# STM32_microcontroller_IOs.net
KiCad netlist of a schematic drawn in Altium Designer
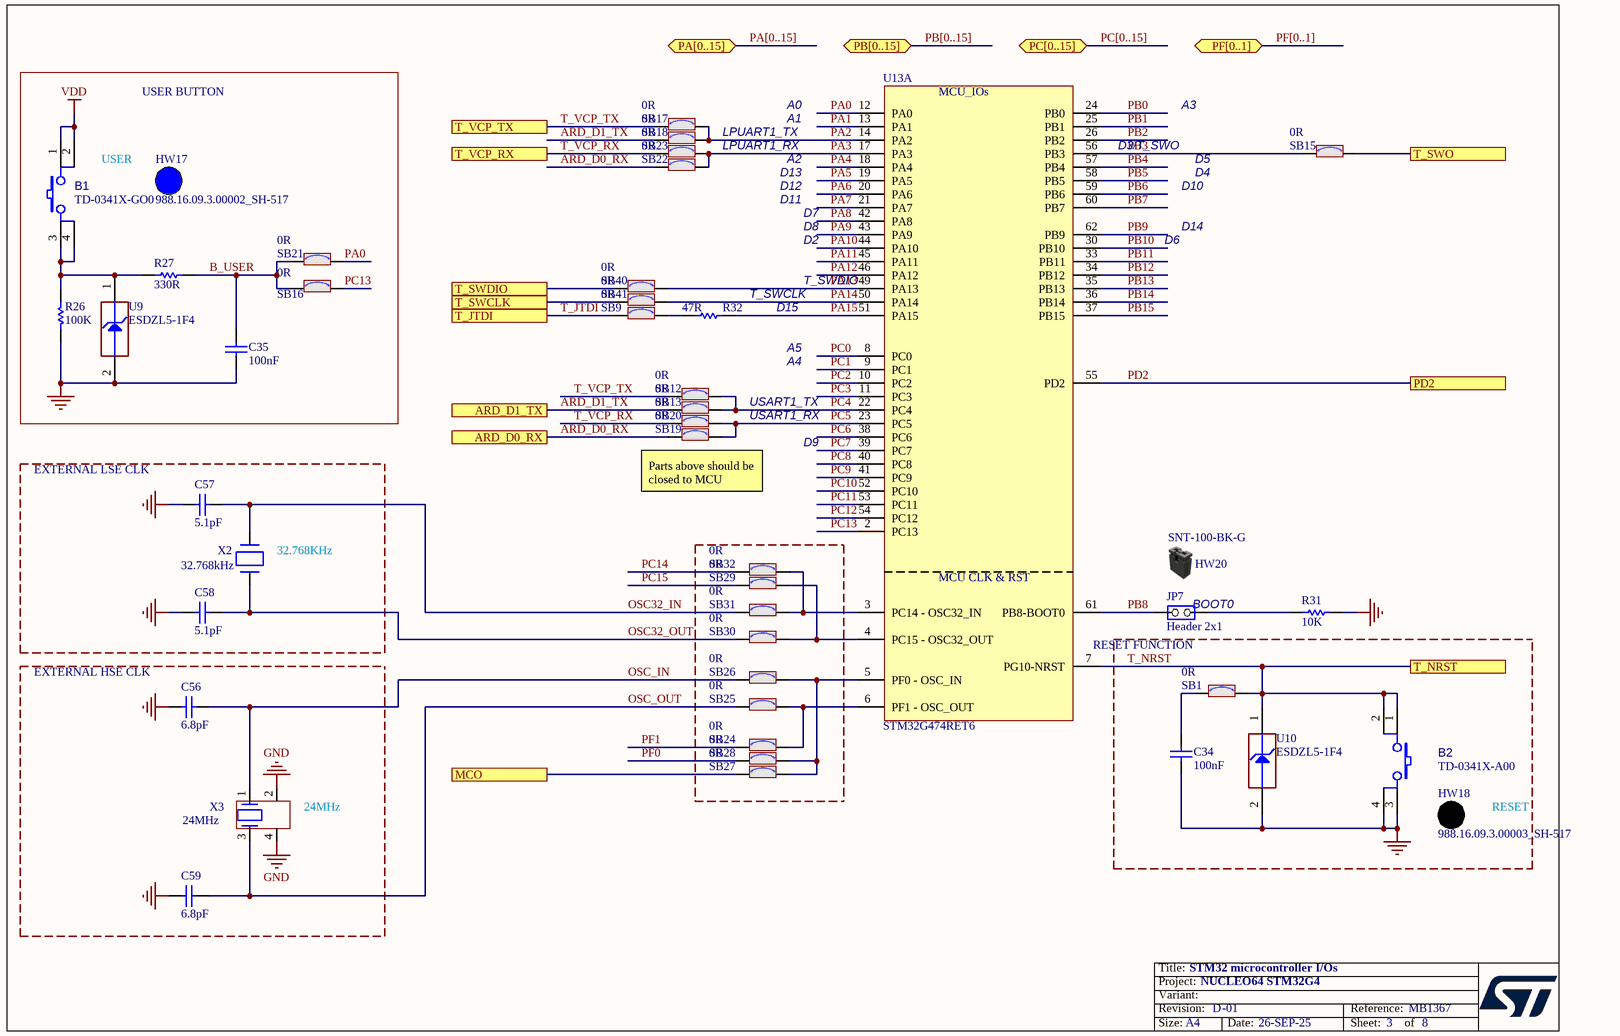
[diagram p0: STM32_microcontroller_IOs.SchDoc]

(export (version "E")
  (design (tool "Eeschema 10.0.6"))
  (components
    (comp (ref "B1")
      (value "TD-0341X-GO0")
      (footprint "SWI_WEALTHMETAL_TD-0341_4P_BLUE")
      (description "Non-Open Push-Button 0.1A 24V")
      (fields
        (field (name "INTERNAL_PART_NUMBER") "MCD-00002")
        (field (name "MANUFACTURER") "WEALTHMETAL")
        (field (name "PROVIDED_BY") "SUBCO")
      )
      (libsource (lib "MCD_PARTS_database") (part "SW-PUSH-CMS"))
    )
    (comp (ref "B2")
      (value "TD-0341X-A00")
      (footprint "SWI_WEALTHMETAL_TD-0341_4P_BLACK")
      (description "Non-Open Push-Button 0.1A 24V BLACK")
      (fields
        (field (name "INTERNAL_PART_NUMBER") "MCD-00001")
        (field (name "MANUFACTURER") "WEALTHMETAL")
        (field (name "PROVIDED_BY") "SUBCO")
      )
      (libsource (lib "MCD_PARTS_database") (part "SW-PUSH-CMS"))
    )
    (comp (ref "C34")
      (value "100nF")
      (footprint "C0402")
      (description "Capacitor, MLCC, 100nF, 16V, X7R, +/-10%, 0402, T=0.5mm")
      (fields
        (field (name "INTERNAL_PART_NUMBER") "MCD-00006")
        (field (name "MANUFACTURER_PART_NUMBER") "CC0402KRX7R7BB104")
      )
      (libsource (lib "MCD_PARTS_database") (part "Capacitor"))
    )
    (comp (ref "C35")
      (value "100nF")
      (footprint "C0402")
      (description "Capacitor, MLCC, 100nF, 16V, X7R, +/-10%, 0402, T=0.5mm")
      (fields
        (field (name "INTERNAL_PART_NUMBER") "MCD-00006")
        (field (name "MANUFACTURER_PART_NUMBER") "CC0402KRX7R7BB104")
      )
      (libsource (lib "MCD_PARTS_database") (part "Capacitor"))
    )
    (comp (ref "C56")
      (value "6.8pF")
      (footprint "C0402")
      (description "Capacitor, MLCC, 6.8pF, 50V, NPO, +-0.25pF, 0402, T=0.5mm")
      (fields
        (field (name "INTERNAL_PART_NUMBER") "MCD-00674")
        (field (name "MANUFACTURER_PART_NUMBER") "CC0402CRNPO9BN6R8")
        (field (name "PROVIDED_BY") "SUBCO")
      )
      (libsource (lib "MCD_PARTS_database") (part "Capacitor"))
    )
    (comp (ref "C57")
      (value "5.1pF")
      (footprint "C0402")
      (description "Capacitor, MLCC, 5.1pF, 50V, NPO, +-0.25pF, 0402, T=0.5mm")
      (fields
        (field (name "INTERNAL_PART_NUMBER") "MCD-00003")
        (field (name "MANUFACTURER_PART_NUMBER") "CC0402CRNPO9BN5R1")
        (field (name "PROVIDED_BY") "SUBCO")
      )
      (libsource (lib "MCD_PARTS_database") (part "Capacitor"))
    )
    (comp (ref "C58")
      (value "5.1pF")
      (footprint "C0402")
      (description "Capacitor, MLCC, 5.1pF, 50V, NPO, +-0.25pF, 0402, T=0.5mm")
      (fields
        (field (name "INTERNAL_PART_NUMBER") "MCD-00003")
        (field (name "MANUFACTURER_PART_NUMBER") "CC0402CRNPO9BN5R1")
        (field (name "PROVIDED_BY") "SUBCO")
      )
      (libsource (lib "MCD_PARTS_database") (part "Capacitor"))
    )
    (comp (ref "C59")
      (value "6.8pF")
      (footprint "C0402")
      (description "Capacitor, MLCC, 6.8pF, 50V, NPO, +-0.25pF, 0402, T=0.5mm")
      (fields
        (field (name "INTERNAL_PART_NUMBER") "MCD-00674")
        (field (name "MANUFACTURER_PART_NUMBER") "CC0402CRNPO9BN6R8")
        (field (name "PROVIDED_BY") "SUBCO")
      )
      (libsource (lib "MCD_PARTS_database") (part "Capacitor"))
    )
    (comp (ref "HW17")
      (value "988.16.09.3.00002_SH-517")
      (description "Blue Hat for switch TD0341X-G01-BLU")
      (fields
        (field (name "INTERNAL_PART_NUMBER") "MCD-00634")
        (field (name "MANUFACTURER") "_A_JIUBABA")
        (field (name "PROVIDED_BY") "SUBCO")
      )
      (libsource (lib "MCD_PARTS_database") (part "BUTTON_HAT_BLUE"))
    )
    (comp (ref "HW18")
      (value "988.16.09.3.00003_SH-517")
      (description "Black Hat for switch TD0341X-G01-BLA")
      (fields
        (field (name "INTERNAL_PART_NUMBER") "MCD-00635")
        (field (name "MANUFACTURER") "_A_JIUBABA")
        (field (name "PROVIDED_BY") "SUBCO")
      )
      (libsource (lib "MCD_PARTS_database") (part "BUTTON_HAT_BLACK"))
    )
    (comp (ref "HW20")
      (value "SNT-100-BK-G")
      (description "SHUNT 2.54mm BLACK")
      (fields
        (field (name "INTERNAL_PART_NUMBER") "MCD-00043")
        (field (name "MANUFACTURER") "SAMTEC")
        (field (name "PROVIDED_BY") "Subcon")
      )
      (libsource (lib "MCD_PARTS_database") (part "Shunt Black 2.54mm"))
    )
    (comp (ref "JP7")
      (value "Header 2x1")
      (footprint "CON_SAMTEC_TSW-102-07-G-S")
      (description "Header, 2x1, 2,54mm, VR, TH, Height 5.84mm/2.54mm")
      (fields
        (field (name "INTERNAL_PART_NUMBER") "MCD-00045")
        (field (name "MANUFACTURER_PART_NUMBER") "TSW-102-07-G-S")
        (field (name "PROVIDED_BY") "Subcon")
      )
      (libsource (lib "MCD_PARTS_database") (part "Jumper_Header 2x1"))
    )
    (comp (ref "R26")
      (value "100K")
      (footprint "R0603")
      (description "Resistor,100K,0603,1%,1/10W")
      (fields
        (field (name "INTERNAL_PART_NUMBER") "MCD-00223")
        (field (name "MANUFACTURER_PART_NUMBER") "RC0603FR-07100KL")
        (field (name "PROVIDED_BY") "Subcon")
      )
      (libsource (lib "MCD_PARTS_database") (part "Resistor"))
    )
    (comp (ref "R27")
      (value "330R")
      (footprint "R0603")
      (description "Resistor,330R,0603,1%,1/10W")
      (fields
        (field (name "INTERNAL_PART_NUMBER") "MCD-00197")
        (field (name "MANUFACTURER_PART_NUMBER") "RC0603FR-07330RL")
        (field (name "PROVIDED_BY") "Subcon")
      )
      (libsource (lib "MCD_PARTS_database") (part "Resistor"))
    )
    (comp (ref "R31")
      (value "10K")
      (footprint "R0603")
      (description "Resistor,10K,0603,1%,1/10W")
      (fields
        (field (name "INTERNAL_PART_NUMBER") "MCD-00220")
        (field (name "MANUFACTURER_PART_NUMBER") "RC0603FR-0710KL")
        (field (name "PROVIDED_BY") "Subcon")
      )
      (libsource (lib "MCD_PARTS_database") (part "Resistor"))
    )
    (comp (ref "R32")
      (value "47R")
      (footprint "R0402")
      (description "Resistor,47R,0402,1%,1/16W")
      (fields
        (field (name "INTERNAL_PART_NUMBER") "MCD-00481")
        (field (name "MANUFACTURER_PART_NUMBER") "RC0402FR-0747RL")
        (field (name "PROVIDED_BY") "SUBCO")
      )
      (libsource (lib "MCD_PARTS_database") (part "Resistor"))
    )
    (comp (ref "SB1")
      (value "0R")
      (footprint "SOLDER-BRIDGE_R0603-0R")
      (description "Solder Bridge ON")
      (fields
        (field (name "INTERNAL_PART_NUMBER") "MCD-00071")
        (field (name "MANUFACTURER_PART_NUMBER") "RC0603JR-070RL")
        (field (name "PROVIDED_BY") "SUBCO")
      )
      (libsource (lib "MCD_PARTS_database") (part "SB_ON"))
    )
    (comp (ref "SB9")
      (value "0R")
      (footprint "SOLDER-BRIDGE_R0603-0R")
      (description "Solder Bridge ON")
      (fields
        (field (name "INTERNAL_PART_NUMBER") "MCD-00071")
        (field (name "MANUFACTURER_PART_NUMBER") "RC0603JR-070RL")
        (field (name "PROVIDED_BY") "SUBCO")
      )
      (libsource (lib "MCD_PARTS_database") (part "SB_ON"))
    )
    (comp (ref "SB12")
      (value "0R")
      (footprint "SOLDER-BRIDGE_R0603-0R")
      (description "Solder Bridge ON")
      (fields
        (field (name "INTERNAL_PART_NUMBER") "MCD-00071")
        (field (name "MANUFACTURER_PART_NUMBER") "RC0603JR-070RL")
        (field (name "PROVIDED_BY") "SUBCO")
      )
      (libsource (lib "MCD_PARTS_database") (part "SB_ON"))
    )
    (comp (ref "SB13")
      (value "0R")
      (footprint "SOLDER-BRIDGE_R0603-0R")
      (description "Solder Bridge ON")
      (fields
        (field (name "INTERNAL_PART_NUMBER") "MCD-00071")
        (field (name "MANUFACTURER_PART_NUMBER") "RC0603JR-070RL")
        (field (name "PROVIDED_BY") "SUBCO")
      )
      (libsource (lib "") (part "SB_ON_1"))
    )
    (comp (ref "SB15")
      (value "0R")
      (footprint "SOLDER-BRIDGE_R0603-0R")
      (description "Solder Bridge ON")
      (fields
        (field (name "INTERNAL_PART_NUMBER") "MCD-00071")
        (field (name "MANUFACTURER_PART_NUMBER") "RC0603JR-070RL")
        (field (name "PROVIDED_BY") "SUBCO")
      )
      (libsource (lib "MCD_PARTS_database") (part "SB_ON"))
    )
    (comp (ref "SB16")
      (value "0R")
      (footprint "SOLDER-BRIDGE_R0603-0R")
      (description "Solder Bridge ON")
      (fields
        (field (name "INTERNAL_PART_NUMBER") "MCD-00071")
        (field (name "MANUFACTURER_PART_NUMBER") "RC0603JR-070RL")
        (field (name "PROVIDED_BY") "SUBCO")
      )
      (libsource (lib "MCD_PARTS_database") (part "SB_ON"))
    )
    (comp (ref "SB17")
      (value "0R")
      (footprint "SOLDER-BRIDGE_R0603-0R")
      (description "Solder Bridge ON")
      (fields
        (field (name "INTERNAL_PART_NUMBER") "MCD-00071")
        (field (name "MANUFACTURER_PART_NUMBER") "RC0603JR-070RL")
        (field (name "PROVIDED_BY") "SUBCO")
      )
      (libsource (lib "MCD_PARTS_database") (part "SB_ON"))
    )
    (comp (ref "SB18")
      (value "0R")
      (footprint "SOLDER-BRIDGE_R0603-0R")
      (description "Solder Bridge ON")
      (fields
        (field (name "INTERNAL_PART_NUMBER") "MCD-00071")
        (field (name "MANUFACTURER_PART_NUMBER") "RC0603JR-070RL")
        (field (name "PROVIDED_BY") "SUBCO")
      )
      (libsource (lib "") (part "SB_ON_1"))
    )
    (comp (ref "SB19")
      (value "0R")
      (footprint "SOLDER-BRIDGE_R0603-0R")
      (description "Solder Bridge ON")
      (fields
        (field (name "INTERNAL_PART_NUMBER") "MCD-00071")
        (field (name "MANUFACTURER_PART_NUMBER") "RC0603JR-070RL")
        (field (name "PROVIDED_BY") "SUBCO")
      )
      (libsource (lib "") (part "SB_ON_1"))
    )
    (comp (ref "SB20")
      (value "0R")
      (footprint "SOLDER-BRIDGE_R0603-0R")
      (description "Solder Bridge ON")
      (fields
        (field (name "INTERNAL_PART_NUMBER") "MCD-00071")
        (field (name "MANUFACTURER_PART_NUMBER") "RC0603JR-070RL")
        (field (name "PROVIDED_BY") "SUBCO")
      )
      (libsource (lib "MCD_PARTS_database") (part "SB_ON"))
    )
    (comp (ref "SB21")
      (value "0R")
      (footprint "SOLDER-BRIDGE_R0603-0R")
      (description "Solder Bridge ON")
      (fields
        (field (name "INTERNAL_PART_NUMBER") "MCD-00071")
        (field (name "MANUFACTURER_PART_NUMBER") "RC0603JR-070RL")
        (field (name "PROVIDED_BY") "SUBCO")
      )
      (libsource (lib "MCD_PARTS_database") (part "SB_ON"))
    )
    (comp (ref "SB22")
      (value "0R")
      (footprint "SOLDER-BRIDGE_R0603-0R")
      (description "Solder Bridge ON")
      (fields
        (field (name "INTERNAL_PART_NUMBER") "MCD-00071")
        (field (name "MANUFACTURER_PART_NUMBER") "RC0603JR-070RL")
        (field (name "PROVIDED_BY") "SUBCO")
      )
      (libsource (lib "") (part "SB_ON_1"))
    )
    (comp (ref "SB23")
      (value "0R")
      (footprint "SOLDER-BRIDGE_R0603-0R")
      (description "Solder Bridge ON")
      (fields
        (field (name "INTERNAL_PART_NUMBER") "MCD-00071")
        (field (name "MANUFACTURER_PART_NUMBER") "RC0603JR-070RL")
        (field (name "PROVIDED_BY") "SUBCO")
      )
      (libsource (lib "MCD_PARTS_database") (part "SB_ON"))
    )
    (comp (ref "SB24")
      (value "0R")
      (footprint "SOLDER-BRIDGE_R0603-0R")
      (description "Solder Bridge ON")
      (fields
        (field (name "INTERNAL_PART_NUMBER") "MCD-00071")
        (field (name "MANUFACTURER_PART_NUMBER") "RC0603JR-070RL")
        (field (name "PROVIDED_BY") "SUBCO")
      )
      (libsource (lib "MCD_PARTS_database") (part "SB_ON"))
    )
    (comp (ref "SB25")
      (value "0R")
      (footprint "SOLDER-BRIDGE_R0603-0R")
      (description "Solder Bridge ON")
      (fields
        (field (name "INTERNAL_PART_NUMBER") "MCD-00071")
        (field (name "MANUFACTURER_PART_NUMBER") "RC0603JR-070RL")
        (field (name "PROVIDED_BY") "SUBCO")
      )
      (libsource (lib "MCD_PARTS_database") (part "SB_ON"))
    )
    (comp (ref "SB26")
      (value "0R")
      (footprint "SOLDER-BRIDGE_R0603-0R")
      (description "Solder Bridge ON")
      (fields
        (field (name "INTERNAL_PART_NUMBER") "MCD-00071")
        (field (name "MANUFACTURER_PART_NUMBER") "RC0603JR-070RL")
        (field (name "PROVIDED_BY") "SUBCO")
      )
      (libsource (lib "MCD_PARTS_database") (part "SB_ON"))
    )
    (comp (ref "SB27")
      (value "0R")
      (footprint "SOLDER-BRIDGE_R0603-0R")
      (description "Solder Bridge ON")
      (fields
        (field (name "INTERNAL_PART_NUMBER") "MCD-00071")
        (field (name "MANUFACTURER_PART_NUMBER") "RC0603JR-070RL")
        (field (name "PROVIDED_BY") "SUBCO")
      )
      (libsource (lib "MCD_PARTS_database") (part "SB_ON"))
    )
    (comp (ref "SB28")
      (value "0R")
      (footprint "SOLDER-BRIDGE_R0603-0R")
      (description "Solder Bridge ON")
      (fields
        (field (name "INTERNAL_PART_NUMBER") "MCD-00071")
        (field (name "MANUFACTURER_PART_NUMBER") "RC0603JR-070RL")
        (field (name "PROVIDED_BY") "SUBCO")
      )
      (libsource (lib "MCD_PARTS_database") (part "SB_ON"))
    )
    (comp (ref "SB29")
      (value "0R")
      (footprint "SOLDER-BRIDGE_R0603-0R")
      (description "Solder Bridge ON")
      (fields
        (field (name "INTERNAL_PART_NUMBER") "MCD-00071")
        (field (name "MANUFACTURER_PART_NUMBER") "RC0603JR-070RL")
        (field (name "PROVIDED_BY") "SUBCO")
      )
      (libsource (lib "MCD_PARTS_database") (part "SB_ON"))
    )
    (comp (ref "SB30")
      (value "0R")
      (footprint "SOLDER-BRIDGE_R0603-0R")
      (description "Solder Bridge ON")
      (fields
        (field (name "INTERNAL_PART_NUMBER") "MCD-00071")
        (field (name "MANUFACTURER_PART_NUMBER") "RC0603JR-070RL")
        (field (name "PROVIDED_BY") "SUBCO")
      )
      (libsource (lib "MCD_PARTS_database") (part "SB_ON"))
    )
    (comp (ref "SB31")
      (value "0R")
      (footprint "SOLDER-BRIDGE_R0603-0R")
      (description "Solder Bridge ON")
      (fields
        (field (name "INTERNAL_PART_NUMBER") "MCD-00071")
        (field (name "MANUFACTURER_PART_NUMBER") "RC0603JR-070RL")
        (field (name "PROVIDED_BY") "SUBCO")
      )
      (libsource (lib "MCD_PARTS_database") (part "SB_ON"))
    )
    (comp (ref "SB32")
      (value "0R")
      (footprint "SOLDER-BRIDGE_R0603-0R")
      (description "Solder Bridge ON")
      (fields
        (field (name "INTERNAL_PART_NUMBER") "MCD-00071")
        (field (name "MANUFACTURER_PART_NUMBER") "RC0603JR-070RL")
        (field (name "PROVIDED_BY") "SUBCO")
      )
      (libsource (lib "MCD_PARTS_database") (part "SB_ON"))
    )
    (comp (ref "SB40")
      (value "0R")
      (footprint "SOLDER-BRIDGE_R0603-0R")
      (description "Solder Bridge ON")
      (fields
        (field (name "INTERNAL_PART_NUMBER") "MCD-00071")
        (field (name "MANUFACTURER_PART_NUMBER") "RC0603JR-070RL")
        (field (name "PROVIDED_BY") "SUBCO")
      )
      (libsource (lib "MCD_PARTS_database") (part "SB_ON"))
    )
    (comp (ref "SB41")
      (value "0R")
      (footprint "SOLDER-BRIDGE_R0603-0R")
      (description "Solder Bridge ON")
      (fields
        (field (name "INTERNAL_PART_NUMBER") "MCD-00071")
        (field (name "MANUFACTURER_PART_NUMBER") "RC0603JR-070RL")
        (field (name "PROVIDED_BY") "SUBCO")
      )
      (libsource (lib "MCD_PARTS_database") (part "SB_ON"))
    )
    (comp (ref "U9")
      (value "ESDZL5-1F4")
      (footprint "ESD_0201_H0P3_1K_2A")
      (description "Diode, ESD TVS, 5V5, 100nA, 10V, 0201")
      (fields
        (field (name "INTERNAL_PART_NUMBER") "MCD-03501")
        (field (name "MANUFACTURER") "STMICROELECTRONICS")
      )
      (libsource (lib "MCD_PARTS_database") (part "ESD-TRANSIL"))
    )
    (comp (ref "U10")
      (value "ESDZL5-1F4")
      (footprint "ESD_0201_H0P3_1K_2A")
      (description "Diode, ESD TVS, 5V5, 100nA, 10V, 0201")
      (fields
        (field (name "INTERNAL_PART_NUMBER") "MCD-03501")
        (field (name "MANUFACTURER") "STMICROELECTRONICS")
      )
      (libsource (lib "MCD_PARTS_database") (part "ESD-TRANSIL"))
    )
    (comp (ref "U13")
      (value "STM32G474RET6")
      (footprint "ICC_LQFP64_10X10_P050_SOCKET_YAMAICHI_IC149-064-069-B5_NM")
      (description "STM32G474, LQFP64 package,  3D IC footprint with 2D socket footprint.")
      (fields
        (field (name "INTERNAL_PART_NUMBER") "MCD-01243")
        (field (name "MANUFACTURER") "STMICROELECTRONICS")
        (field (name "PROVIDED_BY") "SUBCO with ST control")
      )
      (libsource (lib "MCD_PARTS_database") (part "STM32G4xx_LQFP64"))
    )
    (comp (ref "X2")
      (value "32.768kHz")
      (footprint "CRY_NX3215SA_2P")
      (description "Crystal 32.768kHz, 6pF, +-20ppm, 50Kohms max, SMD")
      (fields
        (field (name "INTERNAL_PART_NUMBER") "MCD-00091")
        (field (name "MANUFACTURER_PART_NUMBER") "NX3215SA-32.768KHz-EXS00A-MU00525")
        (field (name "PROVIDED_BY") "SUBCO")
      )
      (libsource (lib "MCD_PARTS_database") (part "XTAL_2_PINS"))
    )
    (comp (ref "X3")
      (value "24MHz")
      (footprint "CRY_NX2016SA_4P")
      (description "Crystal 24MHz, 6pF, +-20ppm, 80ohms max, SMD")
      (fields
        (field (name "INTERNAL_PART_NUMBER") "MCD-01036")
        (field (name "MANUFACTURER_PART_NUMBER") "NX2016SA-24MHz-EXS00A-CS10820")
        (field (name "PROVIDED_BY") "SUBCO")
      )
      (libsource (lib "MCD_PARTS_database") (part "XTAL_4_PINS"))
    )
  )
  (nets
    (net (code "1") (name "/ARD_D0_RX") (class "Default")
      (node (ref "SB19") (pin "2") (pinfunction "2_2") (pintype "passive"))
      (node (ref "SB22") (pin "2") (pinfunction "2_2") (pintype "passive"))
    )
    (net (code "2") (name "/ARD_D1_TX") (class "Default")
      (node (ref "SB13") (pin "2") (pinfunction "2_2") (pintype "passive"))
      (node (ref "SB18") (pin "2") (pinfunction "2_2") (pintype "passive"))
    )
    (net (code "3") (name "/B_USER") (class "Default")
      (node (ref "C35") (pin "2") (pinfunction "2_2") (pintype "passive"))
      (node (ref "R27") (pin "2") (pinfunction "2_2") (pintype "passive"))
      (node (ref "SB16") (pin "1") (pinfunction "1_1") (pintype "passive"))
      (node (ref "SB21") (pin "1") (pinfunction "1_1") (pintype "passive"))
    )
    (net (code "4") (name "/MCO") (class "Default")
      (node (ref "SB27") (pin "1") (pinfunction "1_1") (pintype "passive"))
    )
    (net (code "5") (name "/OSC32_IN") (class "Default")
      (node (ref "C57") (pin "1") (pinfunction "1_1") (pintype "passive"))
      (node (ref "SB31") (pin "1") (pinfunction "1_1") (pintype "passive"))
      (node (ref "X2") (pin "1") (pinfunction "X1_1") (pintype "passive"))
    )
    (net (code "6") (name "/OSC32_OUT") (class "Default")
      (node (ref "C58") (pin "1") (pinfunction "1_1") (pintype "passive"))
      (node (ref "SB30") (pin "1") (pinfunction "1_1") (pintype "passive"))
      (node (ref "X2") (pin "2") (pinfunction "X2_2") (pintype "passive"))
    )
    (net (code "7") (name "/OSC_IN") (class "Default")
      (node (ref "C56") (pin "2") (pinfunction "2_2") (pintype "passive"))
      (node (ref "SB26") (pin "1") (pinfunction "1_1") (pintype "passive"))
      (node (ref "X3") (pin "1") (pinfunction "1_1") (pintype "passive"))
    )
    (net (code "8") (name "/OSC_OUT") (class "Default")
      (node (ref "C59") (pin "2") (pinfunction "2_2") (pintype "passive"))
      (node (ref "SB25") (pin "1") (pinfunction "1_1") (pintype "passive"))
      (node (ref "X3") (pin "3") (pinfunction "3_3") (pintype "passive"))
    )
    (net (code "9") (name "/PA0") (class "Default")
      (node (ref "SB21") (pin "2") (pinfunction "2_2") (pintype "passive"))
      (node (ref "U13") (pin "12") (pinfunction "PA0_12") (pintype "passive"))
    )
    (net (code "10") (name "/PA1") (class "Default")
      (node (ref "U13") (pin "13") (pinfunction "PA1_13") (pintype "passive"))
    )
    (net (code "11") (name "/PA2") (class "Default")
      (node (ref "SB17") (pin "2") (pinfunction "2_2") (pintype "passive"))
      (node (ref "SB18") (pin "1") (pinfunction "1_1") (pintype "passive"))
      (node (ref "U13") (pin "14") (pinfunction "PA2_14") (pintype "passive"))
    )
    (net (code "12") (name "/PA3") (class "Default")
      (node (ref "SB22") (pin "1") (pinfunction "1_1") (pintype "passive"))
      (node (ref "SB23") (pin "2") (pinfunction "2_2") (pintype "passive"))
      (node (ref "U13") (pin "17") (pinfunction "PA3_17") (pintype "passive"))
    )
    (net (code "13") (name "/PA4") (class "Default")
      (node (ref "U13") (pin "18") (pinfunction "PA4_18") (pintype "passive"))
    )
    (net (code "14") (name "/PA5") (class "Default")
      (node (ref "U13") (pin "19") (pinfunction "PA5_19") (pintype "passive"))
    )
    (net (code "15") (name "/PA6") (class "Default")
      (node (ref "U13") (pin "20") (pinfunction "PA6_20") (pintype "passive"))
    )
    (net (code "16") (name "/PA7") (class "Default")
      (node (ref "U13") (pin "21") (pinfunction "PA7_21") (pintype "passive"))
    )
    (net (code "17") (name "/PA8") (class "Default")
      (node (ref "U13") (pin "42") (pinfunction "PA8_42") (pintype "passive"))
    )
    (net (code "18") (name "/PA9") (class "Default")
      (node (ref "U13") (pin "43") (pinfunction "PA9_43") (pintype "passive"))
    )
    (net (code "19") (name "/PA10") (class "Default")
      (node (ref "U13") (pin "44") (pinfunction "PA10_44") (pintype "passive"))
    )
    (net (code "20") (name "/PA11") (class "Default")
      (node (ref "U13") (pin "45") (pinfunction "PA11_45") (pintype "passive"))
    )
    (net (code "21") (name "/PA12") (class "Default")
      (node (ref "U13") (pin "46") (pinfunction "PA12_46") (pintype "passive"))
    )
    (net (code "22") (name "/PA13") (class "Default")
      (node (ref "SB40") (pin "2") (pinfunction "2_2") (pintype "passive"))
      (node (ref "U13") (pin "49") (pinfunction "PA13_49") (pintype "passive"))
    )
    (net (code "23") (name "/PA14") (class "Default")
      (node (ref "SB41") (pin "2") (pinfunction "2_2") (pintype "passive"))
      (node (ref "U13") (pin "50") (pinfunction "PA14_50") (pintype "passive"))
    )
    (net (code "24") (name "/PA15") (class "Default")
      (node (ref "R32") (pin "2") (pinfunction "2_2") (pintype "passive"))
      (node (ref "U13") (pin "51") (pinfunction "PA15_51") (pintype "passive"))
    )
    (net (code "26") (name "/PB0") (class "Default")
      (node (ref "U13") (pin "24") (pinfunction "PB0_24") (pintype "passive"))
    )
    (net (code "27") (name "/PB1") (class "Default")
      (node (ref "U13") (pin "25") (pinfunction "PB1_25") (pintype "passive"))
    )
    (net (code "28") (name "/PB2") (class "Default")
      (node (ref "U13") (pin "26") (pinfunction "PB2_26") (pintype "passive"))
    )
    (net (code "29") (name "/PB3") (class "Default")
      (node (ref "SB15") (pin "1") (pinfunction "1_1") (pintype "passive"))
      (node (ref "U13") (pin "56") (pinfunction "PB3_56") (pintype "passive"))
    )
    (net (code "30") (name "/PB4") (class "Default")
      (node (ref "U13") (pin "57") (pinfunction "PB4_57") (pintype "passive"))
    )
    (net (code "31") (name "/PB5") (class "Default")
      (node (ref "U13") (pin "58") (pinfunction "PB5_58") (pintype "passive"))
    )
    (net (code "32") (name "/PB6") (class "Default")
      (node (ref "U13") (pin "59") (pinfunction "PB6_59") (pintype "passive"))
    )
    (net (code "33") (name "/PB7") (class "Default")
      (node (ref "U13") (pin "60") (pinfunction "PB7_60") (pintype "passive"))
    )
    (net (code "34") (name "/PB8") (class "Default")
      (node (ref "JP7") (pin "1") (pinfunction "COMMON_1") (pintype "passive"))
      (node (ref "U13") (pin "61") (pinfunction "PB8-BOOT0_61") (pintype "passive"))
    )
    (net (code "35") (name "/PB9") (class "Default")
      (node (ref "U13") (pin "62") (pinfunction "PB9_62") (pintype "passive"))
    )
    (net (code "36") (name "/PB10") (class "Default")
      (node (ref "U13") (pin "30") (pinfunction "PB10_30") (pintype "passive"))
    )
    (net (code "37") (name "/PB11") (class "Default")
      (node (ref "U13") (pin "33") (pinfunction "PB11_33") (pintype "passive"))
    )
    (net (code "38") (name "/PB12") (class "Default")
      (node (ref "U13") (pin "34") (pinfunction "PB12_34") (pintype "passive"))
    )
    (net (code "39") (name "/PB13") (class "Default")
      (node (ref "U13") (pin "35") (pinfunction "PB13_35") (pintype "passive"))
    )
    (net (code "40") (name "/PB14") (class "Default")
      (node (ref "U13") (pin "36") (pinfunction "PB14_36") (pintype "passive"))
    )
    (net (code "41") (name "/PB15") (class "Default")
      (node (ref "U13") (pin "37") (pinfunction "PB15_37") (pintype "passive"))
    )
    (net (code "43") (name "/PC0") (class "Default")
      (node (ref "U13") (pin "8") (pinfunction "PC0_8") (pintype "passive"))
    )
    (net (code "44") (name "/PC1") (class "Default")
      (node (ref "U13") (pin "9") (pinfunction "PC1_9") (pintype "passive"))
    )
    (net (code "45") (name "/PC2") (class "Default")
      (node (ref "U13") (pin "10") (pinfunction "PC2_10") (pintype "passive"))
    )
    (net (code "46") (name "/PC3") (class "Default")
      (node (ref "U13") (pin "11") (pinfunction "PC3_11") (pintype "passive"))
    )
    (net (code "47") (name "/PC4") (class "Default")
      (node (ref "SB12") (pin "2") (pinfunction "2_2") (pintype "passive"))
      (node (ref "SB13") (pin "1") (pinfunction "1_1") (pintype "passive"))
      (node (ref "U13") (pin "22") (pinfunction "PC4_22") (pintype "passive"))
    )
    (net (code "48") (name "/PC5") (class "Default")
      (node (ref "SB19") (pin "1") (pinfunction "1_1") (pintype "passive"))
      (node (ref "SB20") (pin "2") (pinfunction "2_2") (pintype "passive"))
      (node (ref "U13") (pin "23") (pinfunction "PC5_23") (pintype "passive"))
    )
    (net (code "49") (name "/PC6") (class "Default")
      (node (ref "U13") (pin "38") (pinfunction "PC6_38") (pintype "passive"))
    )
    (net (code "50") (name "/PC7") (class "Default")
      (node (ref "U13") (pin "39") (pinfunction "PC7_39") (pintype "passive"))
    )
    (net (code "51") (name "/PC8") (class "Default")
      (node (ref "U13") (pin "40") (pinfunction "PC8_40") (pintype "passive"))
    )
    (net (code "52") (name "/PC9") (class "Default")
      (node (ref "U13") (pin "41") (pinfunction "PC9_41") (pintype "passive"))
    )
    (net (code "53") (name "/PC10") (class "Default")
      (node (ref "U13") (pin "52") (pinfunction "PC10_52") (pintype "passive"))
    )
    (net (code "54") (name "/PC11") (class "Default")
      (node (ref "U13") (pin "53") (pinfunction "PC11_53") (pintype "passive"))
    )
    (net (code "55") (name "/PC12") (class "Default")
      (node (ref "U13") (pin "54") (pinfunction "PC12_54") (pintype "passive"))
    )
    (net (code "56") (name "/PC13") (class "Default")
      (node (ref "SB16") (pin "2") (pinfunction "2_2") (pintype "passive"))
      (node (ref "U13") (pin "2") (pinfunction "PC13_2") (pintype "passive"))
    )
    (net (code "57") (name "/PC14") (class "Default")
      (node (ref "SB32") (pin "1") (pinfunction "1_1") (pintype "passive"))
    )
    (net (code "58") (name "/PC15") (class "Default")
      (node (ref "SB29") (pin "1") (pinfunction "1_1") (pintype "passive"))
    )
    (net (code "60") (name "/PD2") (class "Default")
      (node (ref "U13") (pin "55") (pinfunction "PD2_55") (pintype "passive"))
    )
    (net (code "61") (name "/PF0") (class "Default")
      (node (ref "SB28") (pin "1") (pinfunction "1_1") (pintype "passive"))
    )
    (net (code "62") (name "/PF1") (class "Default")
      (node (ref "SB24") (pin "1") (pinfunction "1_1") (pintype "passive"))
    )
    (net (code "64") (name "/T_JTDI") (class "Default")
      (node (ref "SB9") (pin "1") (pinfunction "1_1") (pintype "passive"))
    )
    (net (code "65") (name "/T_NRST") (class "Default")
      (node (ref "B2") (pin "1") (pinfunction "1_1") (pintype "passive"))
      (node (ref "B2") (pin "2") (pinfunction "2_2") (pintype "passive"))
      (node (ref "SB1") (pin "2") (pinfunction "2_2") (pintype "passive"))
      (node (ref "U10") (pin "1") (pinfunction "IO1_1") (pintype "passive"))
      (node (ref "U13") (pin "7") (pinfunction "PG10-NRST_7") (pintype "passive"))
    )
    (net (code "66") (name "/T_SWCLK") (class "Default")
      (node (ref "SB41") (pin "1") (pinfunction "1_1") (pintype "passive"))
    )
    (net (code "67") (name "/T_SWDIO") (class "Default")
      (node (ref "SB40") (pin "1") (pinfunction "1_1") (pintype "passive"))
    )
    (net (code "68") (name "/T_SWO") (class "Default")
      (node (ref "SB15") (pin "2") (pinfunction "2_2") (pintype "passive"))
    )
    (net (code "69") (name "/T_VCP_RX") (class "Default")
      (node (ref "SB20") (pin "1") (pinfunction "1_1") (pintype "passive"))
      (node (ref "SB23") (pin "1") (pinfunction "1_1") (pintype "passive"))
    )
    (net (code "70") (name "/T_VCP_TX") (class "Default")
      (node (ref "SB12") (pin "1") (pinfunction "1_1") (pintype "passive"))
      (node (ref "SB17") (pin "1") (pinfunction "1_1") (pintype "passive"))
    )
    (net (code "71") (name "GND") (class "Default")
      (node (ref "B2") (pin "3") (pinfunction "3_3") (pintype "passive"))
      (node (ref "B2") (pin "4") (pinfunction "4_4") (pintype "passive"))
      (node (ref "C34") (pin "1") (pinfunction "1_1") (pintype "passive"))
      (node (ref "C35") (pin "1") (pinfunction "1_1") (pintype "passive"))
      (node (ref "C56") (pin "1") (pinfunction "1_1") (pintype "passive"))
      (node (ref "C57") (pin "2") (pinfunction "2_2") (pintype "passive"))
      (node (ref "C58") (pin "2") (pinfunction "2_2") (pintype "passive"))
      (node (ref "C59") (pin "1") (pinfunction "1_1") (pintype "passive"))
      (node (ref "R26") (pin "1") (pinfunction "1_1") (pintype "passive"))
      (node (ref "R31") (pin "1") (pinfunction "1_1") (pintype "passive"))
      (node (ref "U10") (pin "2") (pinfunction "GND_2") (pintype "passive"))
      (node (ref "U9") (pin "2") (pinfunction "GND_2") (pintype "passive"))
      (node (ref "X3") (pin "2") (pinfunction "2_2") (pintype "passive"))
      (node (ref "X3") (pin "4") (pinfunction "4_4") (pintype "passive"))
    )
    (net (code "72") (name "Net-(C34-Pad2)") (class "Default")
      (node (ref "C34") (pin "2") (pinfunction "2_2") (pintype "passive"))
      (node (ref "SB1") (pin "1") (pinfunction "1_1") (pintype "passive"))
    )
    (net (code "73") (name "Net-(JP7-NO)") (class "Default")
      (node (ref "JP7") (pin "2") (pinfunction "NO_2") (pintype "passive"))
      (node (ref "R31") (pin "2") (pinfunction "2_2") (pintype "passive"))
    )
    (net (code "74") (name "Net-(R32-Pad1)") (class "Default")
      (node (ref "R32") (pin "1") (pinfunction "1_1") (pintype "passive"))
      (node (ref "SB9") (pin "2") (pinfunction "2_2") (pintype "passive"))
    )
    (net (code "75") (name "Net-(U9-IO1)") (class "Default")
      (node (ref "B1") (pin "3") (pinfunction "3_3") (pintype "passive"))
      (node (ref "B1") (pin "4") (pinfunction "4_4") (pintype "passive"))
      (node (ref "R26") (pin "2") (pinfunction "2_2") (pintype "passive"))
      (node (ref "R27") (pin "1") (pinfunction "1_1") (pintype "passive"))
      (node (ref "U9") (pin "1") (pinfunction "IO1_1") (pintype "passive"))
    )
    (net (code "76") (name "Net-(U13A-PC14_-_OSC32_IN)") (class "Default")
      (node (ref "SB31") (pin "2") (pinfunction "2_2") (pintype "passive"))
      (node (ref "SB32") (pin "2") (pinfunction "2_2") (pintype "passive"))
      (node (ref "U13") (pin "3") (pinfunction "PC14_-_OSC32_IN_3") (pintype "passive"))
    )
    (net (code "77") (name "Net-(U13A-PC15_-_OSC32_OUT)") (class "Default")
      (node (ref "SB29") (pin "2") (pinfunction "2_2") (pintype "passive"))
      (node (ref "SB30") (pin "2") (pinfunction "2_2") (pintype "passive"))
      (node (ref "U13") (pin "4") (pinfunction "PC15_-_OSC32_OUT_4") (pintype "passive"))
    )
    (net (code "78") (name "Net-(U13A-PF0_-_OSC_IN)") (class "Default")
      (node (ref "SB26") (pin "2") (pinfunction "2_2") (pintype "passive"))
      (node (ref "SB27") (pin "2") (pinfunction "2_2") (pintype "passive"))
      (node (ref "SB28") (pin "2") (pinfunction "2_2") (pintype "passive"))
      (node (ref "U13") (pin "5") (pinfunction "PF0_-_OSC_IN_5") (pintype "passive"))
    )
    (net (code "79") (name "Net-(U13A-PF1_-_OSC_OUT)") (class "Default")
      (node (ref "SB24") (pin "2") (pinfunction "2_2") (pintype "passive"))
      (node (ref "SB25") (pin "2") (pinfunction "2_2") (pintype "passive"))
      (node (ref "U13") (pin "6") (pinfunction "PF1_-_OSC_OUT_6") (pintype "passive"))
    )
    (net (code "80") (name "VDD") (class "Default")
      (node (ref "B1") (pin "1") (pinfunction "1_1") (pintype "passive"))
      (node (ref "B1") (pin "2") (pinfunction "2_2") (pintype "passive"))
    )
  )
)
